# Double_Soil_Moisture_Feather_Shield.net
KiCad netlist of a schematic drawn in EasyEDA
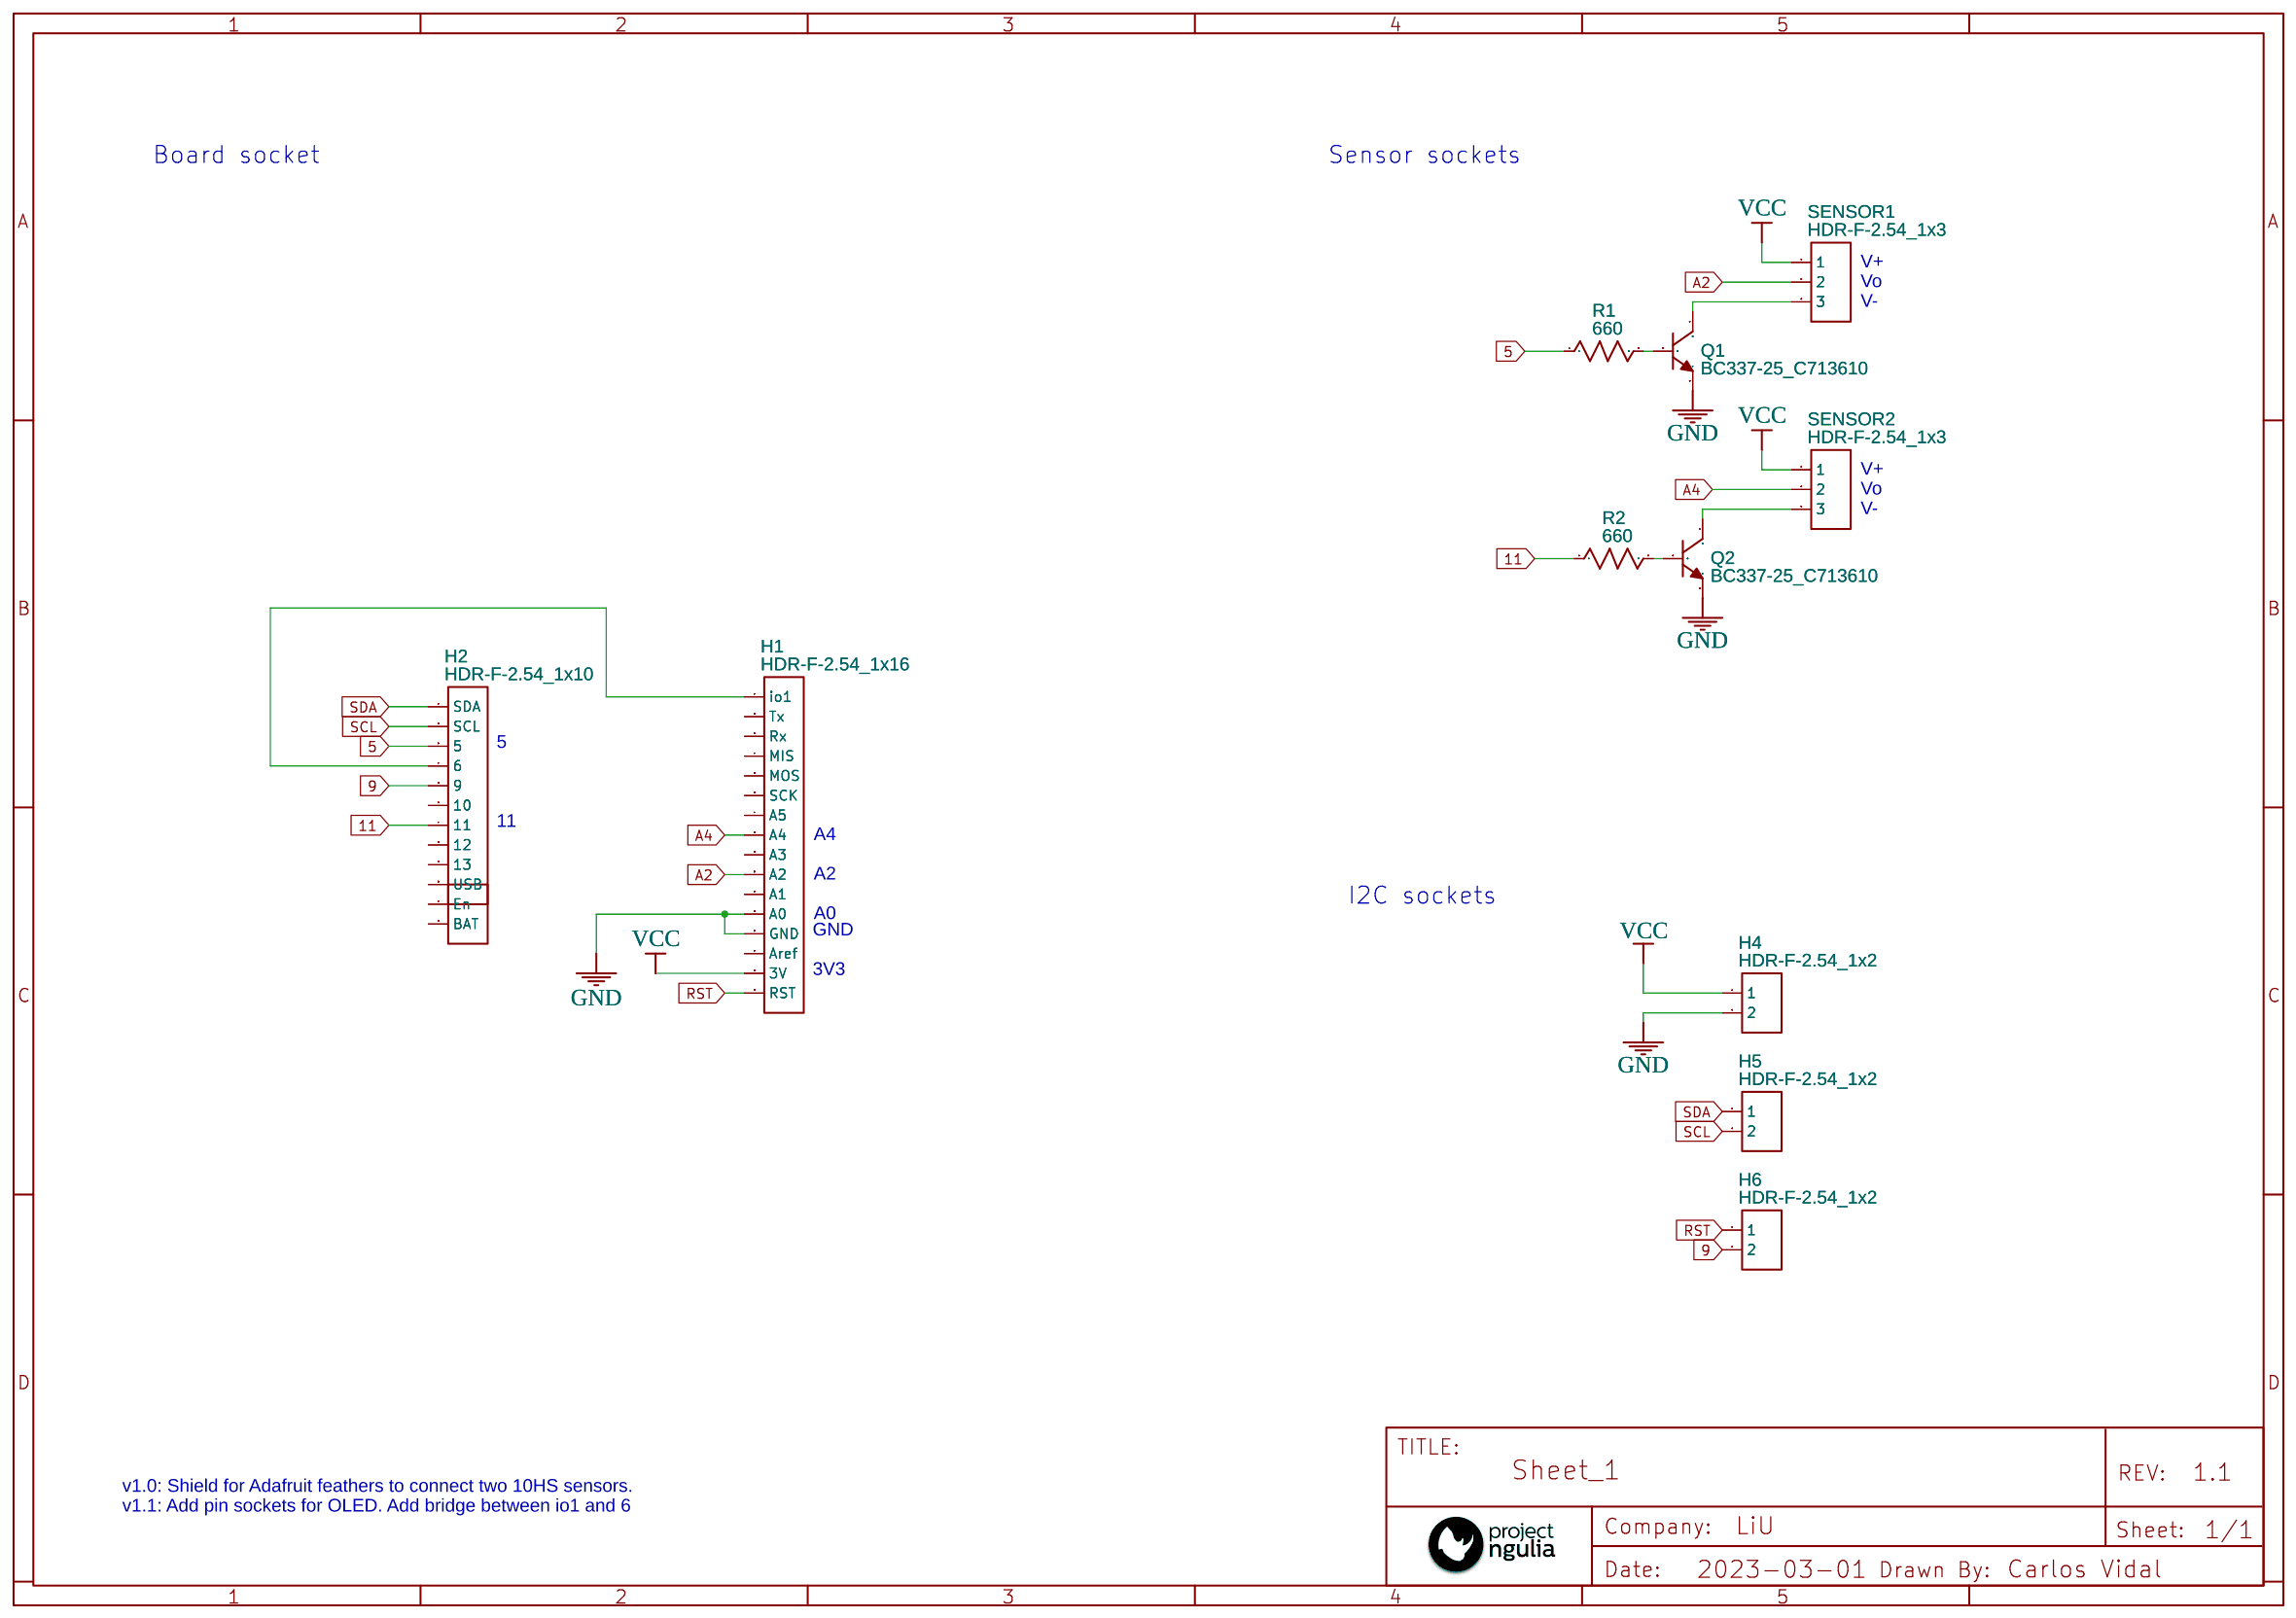
[diagram p0: schematic sheet]

(export (version "E")
  (design (tool "Eeschema 10.0.6"))
  (components
    (comp (ref "H1") (value "HDR-F-2.54_1x16") (libsource (lib "") (part "HDR-F-2.54_1x16")))
    (comp (ref "H2") (value "HDR-F-2.54_1x10") (libsource (lib "") (part "HDR-F-2.54_1x10")))
    (comp (ref "H3") (value "HDR-F-2.54_1x2") (libsource (lib "") (part "HDR-F-2.54_1x2_1")))
    (comp (ref "H4") (value "HDR-F-2.54_1x2") (libsource (lib "") (part "HDR-F-2.54_1x2")))
    (comp (ref "H5") (value "HDR-F-2.54_1x2") (libsource (lib "") (part "HDR-F-2.54_1x2")))
    (comp (ref "H6") (value "HDR-F-2.54_1x2") (libsource (lib "") (part "HDR-F-2.54_1x2")))
    (comp (ref "Q1")
      (value "BC337-25_C713610")
      (fields (field (name "Manufacturer Part") "BC337-25") (field (name "Manufacturer") "LGE(鲁光)"))
      (libsource (lib "") (part "BC337-25_C713610"))
    )
    (comp (ref "Q2")
      (value "BC337-25_C713610")
      (fields (field (name "Manufacturer Part") "BC337-25") (field (name "Manufacturer") "LGE(鲁光)"))
      (libsource (lib "") (part "BC337-25_C713610"))
    )
    (comp (ref "R1") (value "660") (libsource (lib "") (part "R_0603_US")))
    (comp (ref "R2") (value "660") (libsource (lib "") (part "R_0603_US")))
    (comp (ref "SENSOR1") (value "HDR-F-2.54_1x3") (libsource (lib "") (part "HDR-F-2.54_1x3")))
    (comp (ref "SENSOR2") (value "HDR-F-2.54_1x3") (libsource (lib "") (part "HDR-F-2.54_1x3")))
  )
  (nets
    (net (code "1") (name "5") (class "Default")
      (node (ref "H2") (pin "3") (pinfunction "5_3") (pintype "unspecified"))
      (node (ref "R1") (pin "1") (pinfunction "1_1") (pintype "unspecified"))
    )
    (net (code "2") (name "9") (class "Default")
      (node (ref "H2") (pin "5") (pinfunction "9_5") (pintype "unspecified"))
      (node (ref "H6") (pin "2") (pinfunction "2_2") (pintype "input"))
    )
    (net (code "3") (name "11") (class "Default")
      (node (ref "H2") (pin "7") (pinfunction "11_7") (pintype "unspecified"))
      (node (ref "R2") (pin "1") (pinfunction "1_1") (pintype "unspecified"))
    )
    (net (code "4") (name "A2") (class "Default")
      (node (ref "H1") (pin "10") (pinfunction "A2_10") (pintype "unspecified"))
      (node (ref "SENSOR1") (pin "2") (pinfunction "2_2") (pintype "input"))
    )
    (net (code "5") (name "A4") (class "Default")
      (node (ref "H1") (pin "8") (pinfunction "A4_8") (pintype "unspecified"))
      (node (ref "SENSOR2") (pin "2") (pinfunction "2_2") (pintype "input"))
    )
    (net (code "6") (name "GND") (class "Default")
      (node (ref "H1") (pin "12") (pinfunction "A0_12") (pintype "unspecified"))
      (node (ref "H1") (pin "13") (pinfunction "GND_13") (pintype "unspecified"))
      (node (ref "H4") (pin "2") (pinfunction "2_2") (pintype "input"))
      (node (ref "Q1") (pin "3") (pinfunction "E_3") (pintype "input"))
      (node (ref "Q2") (pin "3") (pinfunction "E_3") (pintype "input"))
    )
    (net (code "7") (name "Net-(H1-io1)") (class "Default")
      (node (ref "H1") (pin "1") (pinfunction "io1_1") (pintype "unspecified"))
      (node (ref "H2") (pin "4") (pinfunction "6_4") (pintype "unspecified"))
    )
    (net (code "8") (name "Net-(Q1-B)") (class "Default")
      (node (ref "Q1") (pin "2") (pinfunction "B_2") (pintype "input"))
      (node (ref "R1") (pin "2") (pinfunction "2_2") (pintype "unspecified"))
    )
    (net (code "9") (name "Net-(Q1-C)") (class "Default")
      (node (ref "Q1") (pin "1") (pinfunction "C_1") (pintype "input"))
      (node (ref "SENSOR1") (pin "3") (pinfunction "3_3") (pintype "input"))
    )
    (net (code "10") (name "Net-(Q2-B)") (class "Default")
      (node (ref "Q2") (pin "2") (pinfunction "B_2") (pintype "input"))
      (node (ref "R2") (pin "2") (pinfunction "2_2") (pintype "unspecified"))
    )
    (net (code "11") (name "Net-(Q2-C)") (class "Default")
      (node (ref "Q2") (pin "1") (pinfunction "C_1") (pintype "input"))
      (node (ref "SENSOR2") (pin "3") (pinfunction "3_3") (pintype "input"))
    )
    (net (code "12") (name "RST") (class "Default")
      (node (ref "H1") (pin "16") (pinfunction "RST_16") (pintype "unspecified"))
      (node (ref "H6") (pin "1") (pinfunction "1_1") (pintype "input"))
    )
    (net (code "13") (name "SCL") (class "Default")
      (node (ref "H2") (pin "2") (pinfunction "SCL_2") (pintype "unspecified"))
      (node (ref "H5") (pin "2") (pinfunction "2_2") (pintype "input"))
    )
    (net (code "14") (name "SDA") (class "Default")
      (node (ref "H2") (pin "1") (pinfunction "SDA_1") (pintype "unspecified"))
      (node (ref "H5") (pin "1") (pinfunction "1_1") (pintype "input"))
    )
    (net (code "15") (name "VCC") (class "Default")
      (node (ref "H1") (pin "15") (pinfunction "3V_15") (pintype "unspecified"))
      (node (ref "H4") (pin "1") (pinfunction "1_1") (pintype "input"))
      (node (ref "SENSOR1") (pin "1") (pinfunction "1_1") (pintype "input"))
      (node (ref "SENSOR2") (pin "1") (pinfunction "1_1") (pintype "input"))
    )
    (net (code "16") (name "unconnected-(H1-A1-Pad11)") (class "Default")
      (node (ref "H1") (pin "11") (pinfunction "A1_11") (pintype "unspecified"))
    )
    (net (code "17") (name "unconnected-(H1-A3-Pad9)") (class "Default")
      (node (ref "H1") (pin "9") (pinfunction "A3_9") (pintype "unspecified"))
    )
    (net (code "18") (name "unconnected-(H1-A5-Pad7)") (class "Default")
      (node (ref "H1") (pin "7") (pinfunction "A5_7") (pintype "unspecified"))
    )
    (net (code "19") (name "unconnected-(H1-Aref-Pad14)") (class "Default")
      (node (ref "H1") (pin "14") (pinfunction "Aref_14") (pintype "unspecified"))
    )
    (net (code "20") (name "unconnected-(H1-MIS-Pad4)") (class "Default")
      (node (ref "H1") (pin "4") (pinfunction "MIS_4") (pintype "unspecified"))
    )
    (net (code "21") (name "unconnected-(H1-MOS-Pad5)") (class "Default")
      (node (ref "H1") (pin "5") (pinfunction "MOS_5") (pintype "unspecified"))
    )
    (net (code "22") (name "unconnected-(H1-Rx-Pad3)") (class "Default")
      (node (ref "H1") (pin "3") (pinfunction "Rx_3") (pintype "unspecified"))
    )
    (net (code "23") (name "unconnected-(H1-SCK-Pad6)") (class "Default")
      (node (ref "H1") (pin "6") (pinfunction "SCK_6") (pintype "unspecified"))
    )
    (net (code "24") (name "unconnected-(H1-Tx-Pad2)") (class "Default")
      (node (ref "H1") (pin "2") (pinfunction "Tx_2") (pintype "unspecified"))
    )
    (net (code "25") (name "unconnected-(H2-10-Pad6)") (class "Default")
      (node (ref "H2") (pin "6") (pinfunction "10_6") (pintype "unspecified"))
    )
    (net (code "26") (name "unconnected-(H2-12-Pad8)") (class "Default")
      (node (ref "H2") (pin "8") (pinfunction "12_8") (pintype "unspecified"))
    )
    (net (code "27") (name "unconnected-(H2-13-Pad9)") (class "Default")
      (node (ref "H2") (pin "9") (pinfunction "13_9") (pintype "unspecified"))
    )
    (net (code "28") (name "unconnected-(H2-USB-Pad10)") (class "Default")
      (node (ref "H2") (pin "10") (pinfunction "USB_10") (pintype "unspecified"))
    )
    (net (code "29") (name "unconnected-(H3-BAT-Pad2)") (class "Default")
      (node (ref "H3") (pin "2") (pinfunction "BAT_2") (pintype "input"))
    )
    (net (code "30") (name "unconnected-(H3-En-Pad1)") (class "Default")
      (node (ref "H3") (pin "1") (pinfunction "En_1") (pintype "input"))
    )
  )
)
